# ESP.net
KiCad netlist of a schematic drawn in EAGLE
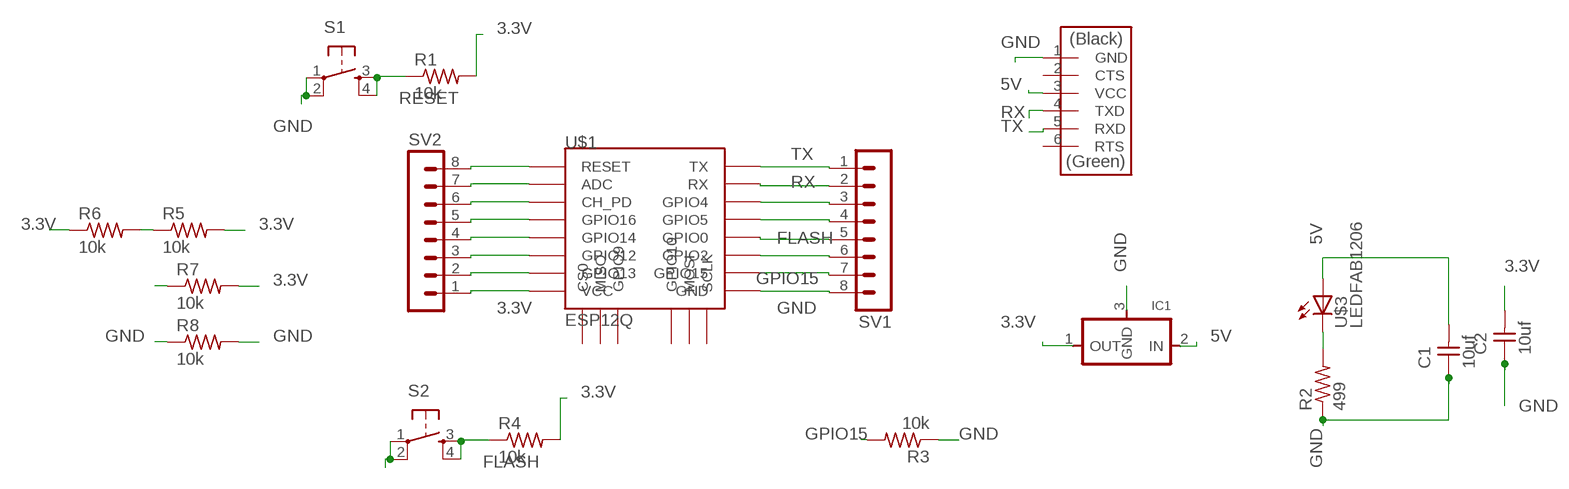
[diagram p0: schematic, sheet 1]

(export (version "E")
  (design (tool "Eeschema 10.0.6"))
  (components
    (comp (ref "C1")
      (value "10uf")
      (footprint "eagle-import:C1206FAB")
      (libsource (lib "eagle-import") (part "CAP-UNPOLARIZEDFAB"))
    )
    (comp (ref "C2")
      (value "10uf")
      (footprint "eagle-import:C1206FAB")
      (libsource (lib "eagle-import") (part "CAP-UNPOLARIZEDFAB"))
    )
    (comp (ref "IC1")
      (value "REGULATORSOT23")
      (footprint "eagle-import:SOT23")
      (libsource (lib "eagle-import") (part "REGULATORSOT23"))
    )
    (comp (ref "R1")
      (value "10k")
      (footprint "eagle-import:R1206FAB")
      (libsource (lib "eagle-import") (part "RES-US1206FAB"))
    )
    (comp (ref "R2")
      (value "499")
      (footprint "eagle-import:R1206FAB")
      (libsource (lib "eagle-import") (part "RES-US1206FAB"))
    )
    (comp (ref "R3")
      (value "10k")
      (footprint "eagle-import:R1206FAB")
      (libsource (lib "eagle-import") (part "RES-US1206FAB"))
    )
    (comp (ref "R4")
      (value "10k")
      (footprint "eagle-import:R1206FAB")
      (libsource (lib "eagle-import") (part "RES-US1206FAB"))
    )
    (comp (ref "R5")
      (value "10k")
      (footprint "eagle-import:R1206FAB")
      (libsource (lib "eagle-import") (part "RES-US1206FAB"))
    )
    (comp (ref "R6")
      (value "10k")
      (footprint "eagle-import:R1206FAB")
      (libsource (lib "eagle-import") (part "RES-US1206FAB"))
    )
    (comp (ref "R7")
      (value "10k")
      (footprint "eagle-import:R1206FAB")
      (libsource (lib "eagle-import") (part "RES-US1206FAB"))
    )
    (comp (ref "R8")
      (value "10k")
      (footprint "eagle-import:R1206FAB")
      (libsource (lib "eagle-import") (part "RES-US1206FAB"))
    )
    (comp (ref "S1")
      (value "6MM_SWITCH6MM_SWITCH")
      (footprint "eagle-import:6MM_SWITCH")
      (libsource (lib "eagle-import") (part "6MM_SWITCH6MM_SWITCH"))
    )
    (comp (ref "S2")
      (value "6MM_SWITCH6MM_SWITCH")
      (footprint "eagle-import:6MM_SWITCH")
      (libsource (lib "eagle-import") (part "6MM_SWITCH6MM_SWITCH"))
    )
    (comp (ref "SV1")
      (value "MA08-1")
      (footprint "eagle-import:MA08-1")
      (libsource (lib "eagle-import") (part "MA08-1"))
    )
    (comp (ref "SV2")
      (value "MA08-1")
      (footprint "eagle-import:MA08-1")
      (libsource (lib "eagle-import") (part "MA08-1"))
    )
    (comp (ref "U$1")
      (value "ESP12Q")
      (footprint "eagle-import:ESP12Q")
      (libsource (lib "eagle-import") (part "ESP12Q"))
    )
    (comp (ref "U$2")
      (value "FTDI-SMD-HEADER")
      (footprint "eagle-import:1X06SMD")
      (libsource (lib "eagle-import") (part "FTDI-SMD-HEADER"))
    )
    (comp (ref "U$3")
      (value "LEDFAB1206")
      (footprint "eagle-import:LED1206FAB")
      (libsource (lib "eagle-import") (part "LEDFAB1206"))
    )
  )
  (nets
    (net (code "1") (name "/3.3V") (class "Default")
      (node (ref "C2") (pin "2") (pinfunction "2_2") (pintype "passive"))
      (node (ref "IC1") (pin "1") (pinfunction "OUT_1") (pintype "bidirectional"))
      (node (ref "R1") (pin "2") (pinfunction "2_2") (pintype "passive"))
      (node (ref "R4") (pin "2") (pinfunction "2_2") (pintype "passive"))
      (node (ref "R5") (pin "1") (pinfunction "1_1") (pintype "passive"))
      (node (ref "R5") (pin "2") (pinfunction "2_2") (pintype "passive"))
      (node (ref "R6") (pin "1") (pinfunction "1_1") (pintype "passive"))
      (node (ref "R6") (pin "2") (pinfunction "2_2") (pintype "passive"))
      (node (ref "R7") (pin "1") (pinfunction "1_1") (pintype "passive"))
      (node (ref "R7") (pin "2") (pinfunction "2_2") (pintype "passive"))
      (node (ref "SV2") (pin "1") (pinfunction "1_1") (pintype "passive"))
      (node (ref "U$1") (pin "VCC") (pinfunction "VCC_VCC") (pintype "bidirectional"))
    )
    (net (code "2") (name "/5V") (class "Default")
      (node (ref "C1") (pin "2") (pinfunction "2_2") (pintype "passive"))
      (node (ref "IC1") (pin "2") (pinfunction "IN_2") (pintype "bidirectional"))
      (node (ref "U$2") (pin "3") (pinfunction "VCC_3") (pintype "bidirectional"))
      (node (ref "U$3") (pin "1") (pinfunction "A_1") (pintype "passive"))
    )
    (net (code "3") (name "/FLASH") (class "Default")
      (node (ref "R4") (pin "1") (pinfunction "1_1") (pintype "passive"))
      (node (ref "S2") (pin "3") (pinfunction "S_3") (pintype "passive"))
      (node (ref "S2") (pin "4") (pinfunction "S1_4") (pintype "passive"))
      (node (ref "SV1") (pin "5") (pinfunction "5_5") (pintype "passive"))
      (node (ref "U$1") (pin "GPIO0") (pinfunction "GPIO0_GPIO0") (pintype "bidirectional"))
    )
    (net (code "4") (name "/GND") (class "Default")
      (node (ref "C1") (pin "1") (pinfunction "1_1") (pintype "passive"))
      (node (ref "C2") (pin "1") (pinfunction "1_1") (pintype "passive"))
      (node (ref "IC1") (pin "3") (pinfunction "GND_3") (pintype "bidirectional"))
      (node (ref "R2") (pin "1") (pinfunction "1_1") (pintype "passive"))
      (node (ref "R3") (pin "1") (pinfunction "1_1") (pintype "passive"))
      (node (ref "R8") (pin "1") (pinfunction "1_1") (pintype "passive"))
      (node (ref "R8") (pin "2") (pinfunction "2_2") (pintype "passive"))
      (node (ref "S1") (pin "1") (pinfunction "P_1") (pintype "passive"))
      (node (ref "S1") (pin "2") (pinfunction "P1_2") (pintype "passive"))
      (node (ref "SV1") (pin "8") (pinfunction "8_8") (pintype "passive"))
      (node (ref "U$1") (pin "GND") (pinfunction "GND_GND") (pintype "bidirectional"))
      (node (ref "U$2") (pin "1") (pinfunction "GND_1") (pintype "bidirectional"))
    )
    (net (code "5") (name "/GPIO15") (class "Default")
      (node (ref "R3") (pin "2") (pinfunction "2_2") (pintype "passive"))
      (node (ref "SV1") (pin "7") (pinfunction "7_7") (pintype "passive"))
      (node (ref "U$1") (pin "GPIO15") (pinfunction "GPIO15_GPIO15") (pintype "bidirectional"))
    )
    (net (code "6") (name "/RESET") (class "Default")
      (node (ref "R1") (pin "1") (pinfunction "1_1") (pintype "passive"))
      (node (ref "S1") (pin "3") (pinfunction "S_3") (pintype "passive"))
      (node (ref "S1") (pin "4") (pinfunction "S1_4") (pintype "passive"))
      (node (ref "SV2") (pin "8") (pinfunction "8_8") (pintype "passive"))
      (node (ref "U$1") (pin "RESET") (pinfunction "RESET_RESET") (pintype "bidirectional"))
    )
    (net (code "7") (name "/RX") (class "Default")
      (node (ref "SV1") (pin "2") (pinfunction "2_2") (pintype "passive"))
      (node (ref "U$1") (pin "RX") (pinfunction "RX_RX") (pintype "bidirectional"))
      (node (ref "U$2") (pin "4") (pinfunction "TXD_4") (pintype "bidirectional"))
    )
    (net (code "8") (name "/TX") (class "Default")
      (node (ref "SV1") (pin "1") (pinfunction "1_1") (pintype "passive"))
      (node (ref "U$1") (pin "TX") (pinfunction "TX_TX") (pintype "bidirectional"))
      (node (ref "U$2") (pin "5") (pinfunction "RXD_5") (pintype "bidirectional"))
    )
    (net (code "9") (name "Net-(S2-P)") (class "Default")
      (node (ref "S2") (pin "1") (pinfunction "P_1") (pintype "passive"))
      (node (ref "S2") (pin "2") (pinfunction "P1_2") (pintype "passive"))
    )
    (net (code "10") (name "Net-(SV1-Pad3)") (class "Default")
      (node (ref "SV1") (pin "3") (pinfunction "3_3") (pintype "passive"))
      (node (ref "U$1") (pin "GPIO4") (pinfunction "GPIO4_GPIO4") (pintype "bidirectional"))
    )
    (net (code "11") (name "Net-(SV1-Pad4)") (class "Default")
      (node (ref "SV1") (pin "4") (pinfunction "4_4") (pintype "passive"))
      (node (ref "U$1") (pin "GPIO5") (pinfunction "GPIO5_GPIO5") (pintype "bidirectional"))
    )
    (net (code "12") (name "Net-(SV1-Pad6)") (class "Default")
      (node (ref "SV1") (pin "6") (pinfunction "6_6") (pintype "passive"))
      (node (ref "U$1") (pin "GPIO2") (pinfunction "GPIO2_GPIO2") (pintype "bidirectional"))
    )
    (net (code "13") (name "Net-(SV2-Pad2)") (class "Default")
      (node (ref "SV2") (pin "2") (pinfunction "2_2") (pintype "passive"))
      (node (ref "U$1") (pin "GPIO13") (pinfunction "GPIO13_GPIO13") (pintype "bidirectional"))
    )
    (net (code "14") (name "Net-(SV2-Pad3)") (class "Default")
      (node (ref "SV2") (pin "3") (pinfunction "3_3") (pintype "passive"))
      (node (ref "U$1") (pin "GPIO12") (pinfunction "GPIO12_GPIO12") (pintype "bidirectional"))
    )
    (net (code "15") (name "Net-(SV2-Pad4)") (class "Default")
      (node (ref "SV2") (pin "4") (pinfunction "4_4") (pintype "passive"))
      (node (ref "U$1") (pin "GPIO14") (pinfunction "GPIO14_GPIO14") (pintype "bidirectional"))
    )
    (net (code "16") (name "Net-(SV2-Pad5)") (class "Default")
      (node (ref "SV2") (pin "5") (pinfunction "5_5") (pintype "passive"))
      (node (ref "U$1") (pin "GPIO16") (pinfunction "GPIO16_GPIO16") (pintype "bidirectional"))
    )
    (net (code "17") (name "Net-(SV2-Pad6)") (class "Default")
      (node (ref "SV2") (pin "6") (pinfunction "6_6") (pintype "passive"))
      (node (ref "U$1") (pin "CH_PD") (pinfunction "CH_PD_CH_PD") (pintype "bidirectional"))
    )
    (net (code "18") (name "Net-(SV2-Pad7)") (class "Default")
      (node (ref "SV2") (pin "7") (pinfunction "7_7") (pintype "passive"))
      (node (ref "U$1") (pin "ADC") (pinfunction "ADC_ADC") (pintype "bidirectional"))
    )
    (net (code "19") (name "Net-(U$3-C)") (class "Default")
      (node (ref "R2") (pin "2") (pinfunction "2_2") (pintype "passive"))
      (node (ref "U$3") (pin "2") (pinfunction "C_2") (pintype "passive"))
    )
    (net (code "20") (name "unconnected-(U$1-PadCS0)") (class "Default")
      (node (ref "U$1") (pin "CS0") (pinfunction "CS0_CS0") (pintype "bidirectional"))
    )
    (net (code "21") (name "unconnected-(U$1-PadGPIO9)") (class "Default")
      (node (ref "U$1") (pin "GPIO9") (pinfunction "GPIO9_GPIO9") (pintype "bidirectional"))
    )
    (net (code "22") (name "unconnected-(U$1-PadGPIO10)") (class "Default")
      (node (ref "U$1") (pin "GPIO10") (pinfunction "GPIO10_GPIO10") (pintype "bidirectional"))
    )
    (net (code "23") (name "unconnected-(U$1-PadMISO)") (class "Default")
      (node (ref "U$1") (pin "MISO") (pinfunction "MISO_MISO") (pintype "bidirectional"))
    )
    (net (code "24") (name "unconnected-(U$1-PadMOSI)") (class "Default")
      (node (ref "U$1") (pin "MOSI") (pinfunction "MOSI_MOSI") (pintype "bidirectional"))
    )
    (net (code "25") (name "unconnected-(U$1-PadSCLK)") (class "Default")
      (node (ref "U$1") (pin "SCLK") (pinfunction "SCLK_SCLK") (pintype "bidirectional"))
    )
    (net (code "26") (name "unconnected-(U$2-CTS-Pad2)") (class "Default")
      (node (ref "U$2") (pin "2") (pinfunction "CTS_2") (pintype "bidirectional"))
    )
    (net (code "27") (name "unconnected-(U$2-RTS-Pad6)") (class "Default")
      (node (ref "U$2") (pin "6") (pinfunction "RTS_6") (pintype "bidirectional"))
    )
  )
)
